# WM8904_mikroBUS_05.net
KiCad netlist of a schematic drawn in EasyEDA Pro
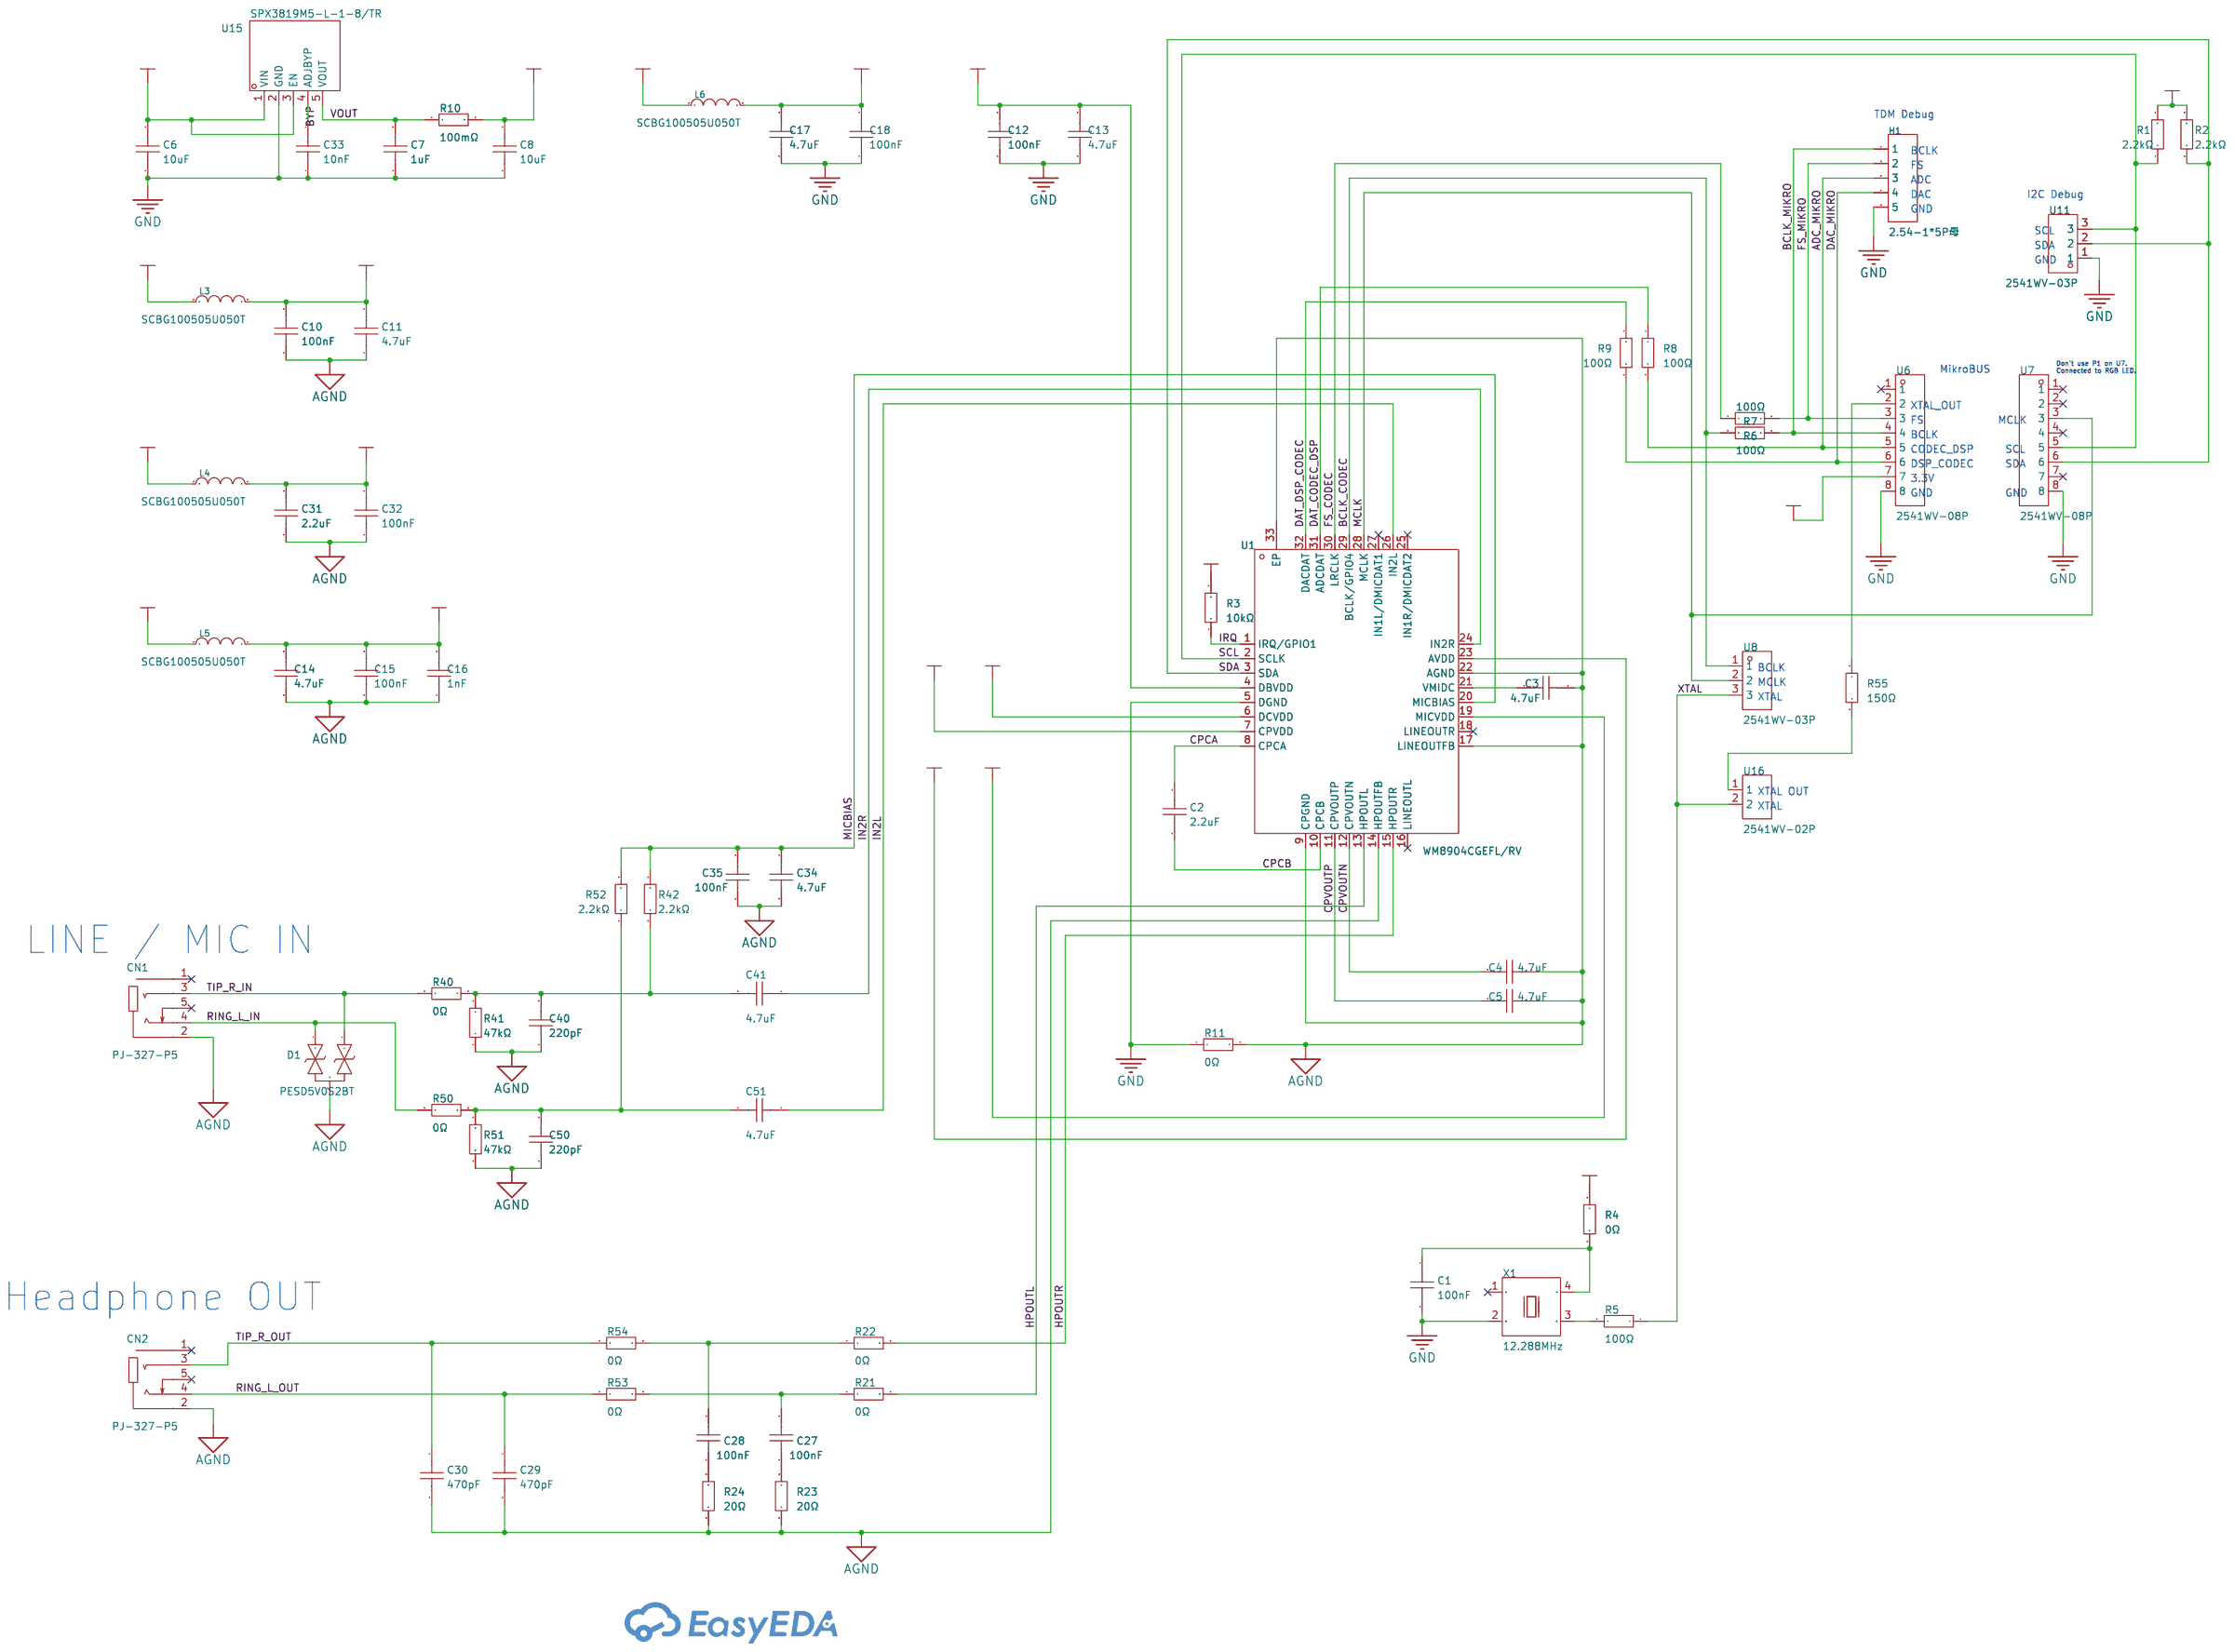
[diagram p0: schematic sheet]

(export (version "E")
  (design (tool "Eeschema 10.0.6"))
  (components
    (comp (ref "C1")
      (value "100nF")
      (footprint "easyedapro:C0603")
      (description "Capacitance:100nF Tolerance:±10% Tolerance:±10% Voltage Rating:50V Temperature Coefficient:X7R")
      (fields
        (field (name "Manufacturer Part") "CC0603KRX7R9BB104")
        (field (name "Manufacturer") "YAGEO(国巨)")
      )
      (libsource (lib "easyedapro") (part "CAP"))
    )
    (comp (ref "C2")
      (value "2.2uF")
      (footprint "easyedapro:C0603")
      (description "Capacitance:2.2uF Tolerance:±10% Tolerance:±10% Voltage Rating:16V Temperature Coefficient:X5R")
      (fields
        (field (name "Manufacturer Part") "CL10A225KO8NNNC")
        (field (name "Manufacturer") "SAMSUNG(三星)")
      )
      (libsource (lib "easyedapro") (part "CAP"))
    )
    (comp (ref "C3")
      (value "4.7uF")
      (footprint "easyedapro:C0603")
      (description "Capacitance:4.7uF Tolerance:±10% Tolerance:±10% Voltage Rating:16V Temperature Coefficient:X5R")
      (fields
        (field (name "Manufacturer Part") "CL10A475KO8NNNC")
        (field (name "Manufacturer") "SAMSUNG(三星)")
      )
      (libsource (lib "easyedapro") (part "CAP"))
    )
    (comp (ref "C4")
      (value "4.7uF")
      (footprint "easyedapro:C0603")
      (description "Capacitance:4.7uF Tolerance:±10% Tolerance:±10% Voltage Rating:16V Temperature Coefficient:X5R")
      (fields
        (field (name "Manufacturer Part") "CL10A475KO8NNNC")
        (field (name "Manufacturer") "SAMSUNG(三星)")
      )
      (libsource (lib "easyedapro") (part "CAP"))
    )
    (comp (ref "C5")
      (value "4.7uF")
      (footprint "easyedapro:C0603")
      (description "Capacitance:4.7uF Tolerance:±10% Tolerance:±10% Voltage Rating:16V Temperature Coefficient:X5R")
      (fields
        (field (name "Manufacturer Part") "CL10A475KO8NNNC")
        (field (name "Manufacturer") "SAMSUNG(三星)")
      )
      (libsource (lib "easyedapro") (part "CAP"))
    )
    (comp (ref "C6")
      (value "10uF")
      (footprint "easyedapro:C0603")
      (description "Capacitance:10uF Tolerance:±10% Tolerance:±10% Voltage Rating:10V Temperature Coefficient:X5R")
      (fields
        (field (name "Manufacturer Part") "CL10A106KP8NNNC")
        (field (name "Manufacturer") "SAMSUNG(三星)")
      )
      (libsource (lib "easyedapro") (part "CAP"))
    )
    (comp (ref "C7")
      (value "1uF")
      (footprint "easyedapro:C0603")
      (description "Capacitance:1uF Tolerance:±10% Tolerance:±10% Voltage Rating:50V Temperature Coefficient:X5R")
      (fields
        (field (name "Manufacturer Part") "CL10A105KB8NNNC")
        (field (name "Manufacturer") "SAMSUNG(三星)")
      )
      (libsource (lib "easyedapro") (part "CAP"))
    )
    (comp (ref "C8")
      (value "10uF")
      (footprint "easyedapro:C0603")
      (description "Capacitance:10uF Tolerance:±10% Tolerance:±10% Voltage Rating:10V Temperature Coefficient:X5R")
      (fields
        (field (name "Manufacturer Part") "CL10A106KP8NNNC")
        (field (name "Manufacturer") "SAMSUNG(三星)")
      )
      (libsource (lib "easyedapro") (part "CAP"))
    )
    (comp (ref "C10")
      (value "100nF")
      (footprint "easyedapro:C0603")
      (description "Capacitance:100nF Tolerance:±10% Tolerance:±10% Voltage Rating:50V Temperature Coefficient:X7R")
      (fields
        (field (name "Manufacturer Part") "CC0603KRX7R9BB104")
        (field (name "Manufacturer") "YAGEO(国巨)")
      )
      (libsource (lib "easyedapro") (part "CAP"))
    )
    (comp (ref "C11")
      (value "4.7uF")
      (footprint "easyedapro:C0603")
      (description "Capacitance:4.7uF Tolerance:±10% Tolerance:±10% Voltage Rating:16V Temperature Coefficient:X5R")
      (fields
        (field (name "Manufacturer Part") "CL10A475KO8NNNC")
        (field (name "Manufacturer") "SAMSUNG(三星)")
      )
      (libsource (lib "easyedapro") (part "CAP"))
    )
    (comp (ref "C12")
      (value "100nF")
      (footprint "easyedapro:C0603")
      (description "Capacitance:100nF Tolerance:±10% Tolerance:±10% Voltage Rating:50V Temperature Coefficient:X7R")
      (fields
        (field (name "Manufacturer Part") "CC0603KRX7R9BB104")
        (field (name "Manufacturer") "YAGEO(国巨)")
      )
      (libsource (lib "easyedapro") (part "CAP"))
    )
    (comp (ref "C13")
      (value "4.7uF")
      (footprint "easyedapro:C0603")
      (description "Capacitance:4.7uF Tolerance:±10% Tolerance:±10% Voltage Rating:16V Temperature Coefficient:X5R")
      (fields
        (field (name "Manufacturer Part") "CL10A475KO8NNNC")
        (field (name "Manufacturer") "SAMSUNG(三星)")
      )
      (libsource (lib "easyedapro") (part "CAP"))
    )
    (comp (ref "C14")
      (value "4.7uF")
      (footprint "easyedapro:C0603")
      (description "Capacitance:4.7uF Tolerance:±10% Tolerance:±10% Voltage Rating:16V Temperature Coefficient:X5R")
      (fields
        (field (name "Manufacturer Part") "CL10A475KO8NNNC")
        (field (name "Manufacturer") "SAMSUNG(三星)")
      )
      (libsource (lib "easyedapro") (part "CAP"))
    )
    (comp (ref "C15")
      (value "100nF")
      (footprint "easyedapro:C0603")
      (description "Capacitance:100nF Tolerance:±10% Tolerance:±10% Voltage Rating:50V Temperature Coefficient:X7R")
      (fields
        (field (name "Manufacturer Part") "CC0603KRX7R9BB104")
        (field (name "Manufacturer") "YAGEO(国巨)")
      )
      (libsource (lib "easyedapro") (part "CAP"))
    )
    (comp (ref "C16")
      (value "1nF")
      (footprint "easyedapro:C0603")
      (description "Capacitance:1nF Tolerance:±10% Tolerance:±10% Voltage Rating:50V Temperature Coefficient:X7R")
      (fields
        (field (name "Manufacturer Part") "CL10B102KB8NNNC")
        (field (name "Manufacturer") "SAMSUNG(三星)")
      )
      (libsource (lib "easyedapro") (part "CAP"))
    )
    (comp (ref "C17")
      (value "4.7uF")
      (footprint "easyedapro:C0603")
      (description "Capacitance:4.7uF Tolerance:±10% Tolerance:±10% Voltage Rating:16V Temperature Coefficient:X5R")
      (fields
        (field (name "Manufacturer Part") "CL10A475KO8NNNC")
        (field (name "Manufacturer") "SAMSUNG(三星)")
      )
      (libsource (lib "easyedapro") (part "CAP"))
    )
    (comp (ref "C18")
      (value "100nF")
      (footprint "easyedapro:C0603")
      (description "Capacitance:100nF Tolerance:±10% Tolerance:±10% Voltage Rating:50V Temperature Coefficient:X7R")
      (fields
        (field (name "Manufacturer Part") "CC0603KRX7R9BB104")
        (field (name "Manufacturer") "YAGEO(国巨)")
      )
      (libsource (lib "easyedapro") (part "CAP"))
    )
    (comp (ref "C27")
      (value "100nF")
      (footprint "easyedapro:C0603")
      (description "Capacitance:100nF Tolerance:±10% Tolerance:±10% Voltage Rating:50V Temperature Coefficient:X7R")
      (fields
        (field (name "Manufacturer Part") "CC0603KRX7R9BB104")
        (field (name "Manufacturer") "YAGEO(国巨)")
      )
      (libsource (lib "easyedapro") (part "CAP"))
    )
    (comp (ref "C28")
      (value "100nF")
      (footprint "easyedapro:C0603")
      (description "Capacitance:100nF Tolerance:±10% Tolerance:±10% Voltage Rating:50V Temperature Coefficient:X7R")
      (fields
        (field (name "Manufacturer Part") "CC0603KRX7R9BB104")
        (field (name "Manufacturer") "YAGEO(国巨)")
      )
      (libsource (lib "easyedapro") (part "CAP"))
    )
    (comp (ref "C29")
      (value "470pF")
      (footprint "easyedapro:C0603")
      (description "Capacitance:470pF Tolerance:±10% Tolerance:±10% Voltage Rating:50V Temperature Coefficient:X7R")
      (fields (field (name "Manufacturer Part") "0603B471K500NT") (field (name "Manufacturer") "FH(风华)"))
      (libsource (lib "easyedapro") (part "CAP"))
    )
    (comp (ref "C30")
      (value "470pF")
      (footprint "easyedapro:C0603")
      (description "Capacitance:470pF Tolerance:±10% Tolerance:±10% Voltage Rating:50V Temperature Coefficient:X7R")
      (fields (field (name "Manufacturer Part") "0603B471K500NT") (field (name "Manufacturer") "FH(风华)"))
      (libsource (lib "easyedapro") (part "CAP"))
    )
    (comp (ref "C31")
      (value "2.2uF")
      (footprint "easyedapro:C0603")
      (description "Capacitance:2.2uF Tolerance:±10% Tolerance:±10% Voltage Rating:16V Temperature Coefficient:X5R")
      (fields
        (field (name "Manufacturer Part") "CL10A225KO8NNNC")
        (field (name "Manufacturer") "SAMSUNG(三星)")
      )
      (libsource (lib "easyedapro") (part "CAP"))
    )
    (comp (ref "C32")
      (value "100nF")
      (footprint "easyedapro:C0603")
      (description "Capacitance:100nF Tolerance:±10% Tolerance:±10% Voltage Rating:50V Temperature Coefficient:X7R")
      (fields
        (field (name "Manufacturer Part") "CC0603KRX7R9BB104")
        (field (name "Manufacturer") "YAGEO(国巨)")
      )
      (libsource (lib "easyedapro") (part "CAP"))
    )
    (comp (ref "C33")
      (value "10nF")
      (footprint "easyedapro:C0603")
      (description "Capacitance:10nF Tolerance:±10% Tolerance:±10% Voltage Rating:50V Temperature Coefficient:X7R")
      (fields (field (name "Manufacturer Part") "0603B103K500NT") (field (name "Manufacturer") "FH(风华)"))
      (libsource (lib "easyedapro") (part "CAP"))
    )
    (comp (ref "C34")
      (value "4.7uF")
      (footprint "easyedapro:C0603")
      (description "Capacitance:4.7uF Tolerance:±10% Tolerance:±10% Voltage Rating:16V Temperature Coefficient:X5R")
      (fields
        (field (name "Manufacturer Part") "CL10A475KO8NNNC")
        (field (name "Manufacturer") "SAMSUNG(三星)")
      )
      (libsource (lib "easyedapro") (part "CAP"))
    )
    (comp (ref "C35")
      (value "100nF")
      (footprint "easyedapro:C0603")
      (description "Capacitance:100nF Tolerance:±10% Tolerance:±10% Voltage Rating:50V Temperature Coefficient:X7R")
      (fields
        (field (name "Manufacturer Part") "CC0603KRX7R9BB104")
        (field (name "Manufacturer") "YAGEO(国巨)")
      )
      (libsource (lib "easyedapro") (part "CAP"))
    )
    (comp (ref "C40")
      (value "220pF")
      (footprint "easyedapro:C0603")
      (description "Capacitance:220pF Tolerance:±10% Tolerance:±10% Voltage Rating:50V Temperature Coefficient:X7R")
      (fields
        (field (name "Manufacturer Part") "CL10B221KB8NNNC")
        (field (name "Manufacturer") "SAMSUNG(三星)")
      )
      (libsource (lib "easyedapro") (part "CAP"))
    )
    (comp (ref "C41")
      (value "4.7uF")
      (footprint "easyedapro:C0603")
      (description "Capacitance:4.7uF Tolerance:±10% Tolerance:±10% Voltage Rating:16V Temperature Coefficient:X5R")
      (fields
        (field (name "Manufacturer Part") "CL10A475KO8NNNC")
        (field (name "Manufacturer") "SAMSUNG(三星)")
      )
      (libsource (lib "easyedapro") (part "CAP"))
    )
    (comp (ref "C50")
      (value "220pF")
      (footprint "easyedapro:C0603")
      (description "Capacitance:220pF Tolerance:±10% Tolerance:±10% Voltage Rating:50V Temperature Coefficient:X7R")
      (fields
        (field (name "Manufacturer Part") "CL10B221KB8NNNC")
        (field (name "Manufacturer") "SAMSUNG(三星)")
      )
      (libsource (lib "easyedapro") (part "CAP"))
    )
    (comp (ref "C51")
      (value "4.7uF")
      (footprint "easyedapro:C0603")
      (description "Capacitance:4.7uF Tolerance:±10% Tolerance:±10% Voltage Rating:16V Temperature Coefficient:X5R")
      (fields
        (field (name "Manufacturer Part") "CL10A475KO8NNNC")
        (field (name "Manufacturer") "SAMSUNG(三星)")
      )
      (libsource (lib "easyedapro") (part "CAP"))
    )
    (comp (ref "CN1")
      (value "PJ-327-P5")
      (footprint "easyedapro:AUDIO-TH_PJ-327-P5")
      (fields (field (name "Manufacturer") "SOFNG(硕方)"))
      (libsource (lib "easyedapro") (part "PJ-327-P5"))
    )
    (comp (ref "CN2")
      (value "PJ-327-P5")
      (footprint "easyedapro:AUDIO-TH_PJ-327-P5")
      (fields (field (name "Manufacturer") "SOFNG(硕方)"))
      (libsource (lib "easyedapro") (part "PJ-327-P5"))
    )
    (comp (ref "D1")
      (value "PESD5V0S2BT")
      (footprint "easyedapro:SOT-23-3_L2.9-W1.3-P1.90-LS2.4-BR")
      (fields (field (name "Manufacturer") "GOODWORK(固得沃克)"))
      (libsource (lib "easyedapro") (part "PESD5V0S2BT_C28310457"))
    )
    (comp (ref "H1")
      (value "2.54-1*5P母")
      (footprint "easyedapro:HDR-TH_5P-P2.54-V-F")
      (fields (field (name "Manufacturer") "BOOMELE(博穆精密)"))
      (libsource (lib "easyedapro") (part "Header-Female-2.54_1x5"))
    )
    (comp (ref "L3")
      (value "SCBG100505U050T")
      (footprint "easyedapro:L0402")
      (fields (field (name "Manufacturer") "Yanchuang(研创)"))
      (libsource (lib "easyedapro") (part "SCBG100505U050T"))
    )
    (comp (ref "L4")
      (value "SCBG100505U050T")
      (footprint "easyedapro:L0402")
      (fields (field (name "Manufacturer") "Yanchuang(研创)"))
      (libsource (lib "easyedapro") (part "SCBG100505U050T"))
    )
    (comp (ref "L5")
      (value "SCBG100505U050T")
      (footprint "easyedapro:L0402")
      (fields (field (name "Manufacturer") "Yanchuang(研创)"))
      (libsource (lib "easyedapro") (part "SCBG100505U050T"))
    )
    (comp (ref "L6")
      (value "SCBG100505U050T")
      (footprint "easyedapro:L0402")
      (fields (field (name "Manufacturer") "Yanchuang(研创)"))
      (libsource (lib "easyedapro") (part "SCBG100505U050T"))
    )
    (comp (ref "R1")
      (value "2.2kΩ")
      (footprint "easyedapro:R0603")
      (fields
        (field (name "Manufacturer Part") "0603WAF2201T5E")
        (field (name "Manufacturer") "UNI-ROYAL(厚声)")
      )
      (libsource (lib "easyedapro") (part "Res"))
    )
    (comp (ref "R2")
      (value "2.2kΩ")
      (footprint "easyedapro:R0603")
      (fields
        (field (name "Manufacturer Part") "0603WAF2201T5E")
        (field (name "Manufacturer") "UNI-ROYAL(厚声)")
      )
      (libsource (lib "easyedapro") (part "Res"))
    )
    (comp (ref "R3")
      (value "10kΩ")
      (footprint "easyedapro:R0603")
      (fields
        (field (name "Manufacturer Part") "0603WAF1002T5E")
        (field (name "Manufacturer") "UNI-ROYAL(厚声)")
      )
      (libsource (lib "easyedapro") (part "Res"))
    )
    (comp (ref "R4")
      (value "0Ω")
      (footprint "easyedapro:R0603")
      (fields
        (field (name "Manufacturer Part") "0603WAF0000T5E")
        (field (name "Manufacturer") "UNI-ROYAL(厚声)")
      )
      (libsource (lib "easyedapro") (part "Res"))
    )
    (comp (ref "R5")
      (value "100Ω")
      (footprint "easyedapro:R0603")
      (fields
        (field (name "Manufacturer Part") "0603WAF1000T5E")
        (field (name "Manufacturer") "UNI-ROYAL(厚声)")
      )
      (libsource (lib "easyedapro") (part "Res"))
    )
    (comp (ref "R6")
      (value "100Ω")
      (footprint "easyedapro:R0603")
      (fields
        (field (name "Manufacturer Part") "0603WAF1000T5E")
        (field (name "Manufacturer") "UNI-ROYAL(厚声)")
      )
      (libsource (lib "easyedapro") (part "Res"))
    )
    (comp (ref "R7")
      (value "100Ω")
      (footprint "easyedapro:R0603")
      (fields
        (field (name "Manufacturer Part") "0603WAF1000T5E")
        (field (name "Manufacturer") "UNI-ROYAL(厚声)")
      )
      (libsource (lib "easyedapro") (part "Res"))
    )
    (comp (ref "R8")
      (value "100Ω")
      (footprint "easyedapro:R0603")
      (fields
        (field (name "Manufacturer Part") "0603WAF1000T5E")
        (field (name "Manufacturer") "UNI-ROYAL(厚声)")
      )
      (libsource (lib "easyedapro") (part "Res"))
    )
    (comp (ref "R9")
      (value "100Ω")
      (footprint "easyedapro:R0603")
      (fields
        (field (name "Manufacturer Part") "0603WAF1000T5E")
        (field (name "Manufacturer") "UNI-ROYAL(厚声)")
      )
      (libsource (lib "easyedapro") (part "Res"))
    )
    (comp (ref "R10")
      (value "100mΩ")
      (footprint "easyedapro:R0603")
      (fields
        (field (name "Manufacturer Part") "0603WAJ010KT5E")
        (field (name "Manufacturer") "UNI-ROYAL(厚声)")
      )
      (libsource (lib "easyedapro") (part "Res"))
    )
    (comp (ref "R11")
      (value "0Ω")
      (footprint "easyedapro:R0603")
      (fields
        (field (name "Manufacturer Part") "0603WAF0000T5E")
        (field (name "Manufacturer") "UNI-ROYAL(厚声)")
      )
      (libsource (lib "easyedapro") (part "Res"))
    )
    (comp (ref "R21")
      (value "0Ω")
      (footprint "easyedapro:R0603")
      (fields
        (field (name "Manufacturer Part") "0603WAF0000T5E")
        (field (name "Manufacturer") "UNI-ROYAL(厚声)")
      )
      (libsource (lib "easyedapro") (part "Res"))
    )
    (comp (ref "R22")
      (value "0Ω")
      (footprint "easyedapro:R0603")
      (fields
        (field (name "Manufacturer Part") "0603WAF0000T5E")
        (field (name "Manufacturer") "UNI-ROYAL(厚声)")
      )
      (libsource (lib "easyedapro") (part "Res"))
    )
    (comp (ref "R23")
      (value "20Ω")
      (footprint "easyedapro:R0603")
      (fields
        (field (name "Manufacturer Part") "0603WAF200JT5E")
        (field (name "Manufacturer") "UNI-ROYAL(厚声)")
      )
      (libsource (lib "easyedapro") (part "Res"))
    )
    (comp (ref "R24")
      (value "20Ω")
      (footprint "easyedapro:R0603")
      (fields
        (field (name "Manufacturer Part") "0603WAF200JT5E")
        (field (name "Manufacturer") "UNI-ROYAL(厚声)")
      )
      (libsource (lib "easyedapro") (part "Res"))
    )
    (comp (ref "R40")
      (value "0Ω")
      (footprint "easyedapro:R0603")
      (fields
        (field (name "Manufacturer Part") "0603WAF0000T5E")
        (field (name "Manufacturer") "UNI-ROYAL(厚声)")
      )
      (libsource (lib "easyedapro") (part "Res"))
    )
    (comp (ref "R41")
      (value "47kΩ")
      (footprint "easyedapro:R0603")
      (fields
        (field (name "Manufacturer Part") "0603WAF4702T5E")
        (field (name "Manufacturer") "UNI-ROYAL(厚声)")
      )
      (libsource (lib "easyedapro") (part "Res"))
    )
    (comp (ref "R42")
      (value "2.2kΩ")
      (footprint "easyedapro:R0603")
      (fields
        (field (name "Manufacturer Part") "0603WAF2201T5E")
        (field (name "Manufacturer") "UNI-ROYAL(厚声)")
      )
      (libsource (lib "easyedapro") (part "Res"))
    )
    (comp (ref "R50")
      (value "0Ω")
      (footprint "easyedapro:R0603")
      (fields
        (field (name "Manufacturer Part") "0603WAF0000T5E")
        (field (name "Manufacturer") "UNI-ROYAL(厚声)")
      )
      (libsource (lib "easyedapro") (part "Res"))
    )
    (comp (ref "R51")
      (value "47kΩ")
      (footprint "easyedapro:R0603")
      (fields
        (field (name "Manufacturer Part") "0603WAF4702T5E")
        (field (name "Manufacturer") "UNI-ROYAL(厚声)")
      )
      (libsource (lib "easyedapro") (part "Res"))
    )
    (comp (ref "R52")
      (value "2.2kΩ")
      (footprint "easyedapro:R0603")
      (fields
        (field (name "Manufacturer Part") "0603WAF2201T5E")
        (field (name "Manufacturer") "UNI-ROYAL(厚声)")
      )
      (libsource (lib "easyedapro") (part "Res"))
    )
    (comp (ref "R53")
      (value "0Ω")
      (footprint "easyedapro:R0603")
      (fields
        (field (name "Manufacturer Part") "0603WAF0000T5E")
        (field (name "Manufacturer") "UNI-ROYAL(厚声)")
      )
      (libsource (lib "easyedapro") (part "Res"))
    )
    (comp (ref "R54")
      (value "0Ω")
      (footprint "easyedapro:R0603")
      (fields
        (field (name "Manufacturer Part") "0603WAF0000T5E")
        (field (name "Manufacturer") "UNI-ROYAL(厚声)")
      )
      (libsource (lib "easyedapro") (part "Res"))
    )
    (comp (ref "R55")
      (value "150Ω")
      (footprint "easyedapro:R0603")
      (fields
        (field (name "Manufacturer Part") "0603WAF1500T5E")
        (field (name "Manufacturer") "UNI-ROYAL(厚声)")
      )
      (libsource (lib "easyedapro") (part "Res"))
    )
    (comp (ref "U1")
      (value "WM8904CGEFL/RV")
      (footprint "easyedapro:QFN-32_L4.0-W4.0-P0.40-BL-EP2.7")
      (fields (field (name "Manufacturer") "Cirrus Logic(凌云)"))
      (libsource (lib "easyedapro") (part "WM8904CGEFL/RV"))
    )
    (comp (ref "U6")
      (value "2541WV-08P")
      (footprint "easyedapro:HDR-TH_8P-P2.54-V-M-4")
      (fields (field (name "Manufacturer") "HanElectricity(瀚源)"))
      (libsource (lib "easyedapro") (part "2541WV-08P"))
    )
    (comp (ref "U7")
      (value "2541WV-08P")
      (footprint "easyedapro:HDR-TH_8P-P2.54-V-M-4")
      (fields (field (name "Manufacturer") "HanElectricity(瀚源)"))
      (libsource (lib "easyedapro") (part "2541WV-08P"))
    )
    (comp (ref "U8")
      (value "2541WV-03P")
      (footprint "easyedapro:HDR-TH_3P-P2.54-V-M-2")
      (fields (field (name "Manufacturer") "HanElectricity(瀚源)"))
      (libsource (lib "easyedapro") (part "2541WV-03P"))
    )
    (comp (ref "U11")
      (value "2541WV-03P")
      (footprint "easyedapro:HDR-TH_3P-P2.54-V-M-2")
      (fields (field (name "Manufacturer") "HanElectricity(瀚源)"))
      (libsource (lib "easyedapro") (part "2541WV-03P"))
    )
    (comp (ref "U15")
      (value "SPX3819M5-L-1-8/TR")
      (footprint "easyedapro:SOT-23-5_L3.0-W1.7-P0.95-LS2.8-TL")
      (fields (field (name "Manufacturer") "MaxLinear(迈凌)"))
      (libsource (lib "easyedapro") (part "SPX3819M5-L-1-8"))
    )
    (comp (ref "U16")
      (value "2541WV-02P")
      (footprint "easyedapro:HDR-TH_2P-P2.54-V-M-1")
      (fields (field (name "Manufacturer") "HanElectricity(瀚源)"))
      (libsource (lib "easyedapro") (part "2541WV-02P"))
    )
    (comp (ref "X1")
      (value "12.288MHz")
      (footprint "easyedapro:OSC-SMD_4P-L2.5-W2.0-BL")
      (fields (field (name "Manufacturer Part") "X1G0041710019") (field (name "Manufacturer") "EPSON(爱普生)"))
      (libsource (lib "easyedapro") (part "X1G004171001900"))
    )
  )
  (nets
    (net (code "1") (name "+3.3V") (class "Default")
      (node (ref "C12") (pin "2") (pinfunction "2_2") (pintype "input"))
      (node (ref "C13") (pin "2") (pinfunction "2_2") (pintype "input"))
      (node (ref "C6") (pin "2") (pinfunction "2_2") (pintype "input"))
      (node (ref "L3") (pin "1") (pinfunction "1_1") (pintype "input"))
      (node (ref "R1") (pin "2") (pinfunction "2_2") (pintype "input"))
      (node (ref "R2") (pin "2") (pinfunction "2_2") (pintype "input"))
      (node (ref "R3") (pin "2") (pinfunction "2_2") (pintype "input"))
      (node (ref "R4") (pin "2") (pinfunction "2_2") (pintype "input"))
      (node (ref "U1") (pin "4") (pinfunction "DBVDD_4") (pintype "unspecified"))
      (node (ref "U15") (pin "1") (pinfunction "VIN_1") (pintype "unspecified"))
      (node (ref "U15") (pin "3") (pinfunction "EN_3") (pintype "unspecified"))
      (node (ref "U6") (pin "7") (pinfunction "7_7") (pintype "unspecified"))
    )
    (net (code "2") (name "/ADC_MIKRO") (class "Default")
      (node (ref "H1") (pin "3") (pinfunction "3_3") (pintype "input"))
      (node (ref "R8") (pin "2") (pinfunction "2_2") (pintype "input"))
      (node (ref "U6") (pin "5") (pinfunction "5_5") (pintype "unspecified"))
    )
    (net (code "3") (name "/BCLK_CODEC") (class "Default")
      (node (ref "R6") (pin "2") (pinfunction "2_2") (pintype "input"))
      (node (ref "U1") (pin "29") (pinfunction "BCLK/GPIO4_29") (pintype "unspecified"))
      (node (ref "U8") (pin "1") (pinfunction "1_1") (pintype "unspecified"))
    )
    (net (code "4") (name "/BCLK_MIKRO") (class "Default")
      (node (ref "H1") (pin "1") (pinfunction "1_1") (pintype "input"))
      (node (ref "R6") (pin "1") (pinfunction "1_1") (pintype "input"))
      (node (ref "U6") (pin "4") (pinfunction "4_4") (pintype "unspecified"))
    )
    (net (code "5") (name "/BYP") (class "Default")
      (node (ref "C33") (pin "2") (pinfunction "2_2") (pintype "input"))
      (node (ref "U15") (pin "4") (pinfunction "ADJBYP_4") (pintype "unspecified"))
    )
    (net (code "6") (name "/CPCA") (class "Default")
      (node (ref "C2") (pin "1") (pinfunction "1_1") (pintype "input"))
      (node (ref "U1") (pin "8") (pinfunction "CPCA_8") (pintype "unspecified"))
    )
    (net (code "7") (name "/CPCB") (class "Default")
      (node (ref "C2") (pin "2") (pinfunction "2_2") (pintype "input"))
      (node (ref "U1") (pin "10") (pinfunction "CPCB_10") (pintype "unspecified"))
    )
    (net (code "8") (name "/CPVOUTN") (class "Default")
      (node (ref "C4") (pin "2") (pinfunction "2_2") (pintype "input"))
      (node (ref "U1") (pin "12") (pinfunction "CPVOUTN_12") (pintype "unspecified"))
    )
    (net (code "9") (name "/CPVOUTP") (class "Default")
      (node (ref "C5") (pin "2") (pinfunction "2_2") (pintype "input"))
      (node (ref "U1") (pin "11") (pinfunction "CPVOUTP_11") (pintype "unspecified"))
    )
    (net (code "10") (name "/DAC_MIKRO") (class "Default")
      (node (ref "H1") (pin "4") (pinfunction "4_4") (pintype "input"))
      (node (ref "R9") (pin "2") (pinfunction "2_2") (pintype "input"))
      (node (ref "U6") (pin "6") (pinfunction "6_6") (pintype "unspecified"))
    )
    (net (code "11") (name "/DAT_CODEC_DSP") (class "Default")
      (node (ref "R8") (pin "1") (pinfunction "1_1") (pintype "input"))
      (node (ref "U1") (pin "31") (pinfunction "ADCDAT_31") (pintype "unspecified"))
    )
    (net (code "12") (name "/DAT_DSP_CODEC") (class "Default")
      (node (ref "R9") (pin "1") (pinfunction "1_1") (pintype "input"))
      (node (ref "U1") (pin "32") (pinfunction "DACDAT_32") (pintype "unspecified"))
    )
    (net (code "13") (name "/FS_CODEC") (class "Default")
      (node (ref "R7") (pin "1") (pinfunction "1_1") (pintype "input"))
      (node (ref "U1") (pin "30") (pinfunction "LRCLK_30") (pintype "unspecified"))
    )
    (net (code "14") (name "/FS_MIKRO") (class "Default")
      (node (ref "H1") (pin "2") (pinfunction "2_2") (pintype "input"))
      (node (ref "R7") (pin "2") (pinfunction "2_2") (pintype "input"))
      (node (ref "U6") (pin "3") (pinfunction "3_3") (pintype "unspecified"))
    )
    (net (code "15") (name "/HPOUTL") (class "Default")
      (node (ref "R21") (pin "2") (pinfunction "2_2") (pintype "input"))
      (node (ref "U1") (pin "13") (pinfunction "HPOUTL_13") (pintype "unspecified"))
    )
    (net (code "16") (name "/HPOUTR") (class "Default")
      (node (ref "R22") (pin "2") (pinfunction "2_2") (pintype "input"))
      (node (ref "U1") (pin "15") (pinfunction "HPOUTR_15") (pintype "unspecified"))
    )
    (net (code "17") (name "/IN2L") (class "Default")
      (node (ref "C51") (pin "1") (pinfunction "1_1") (pintype "input"))
      (node (ref "U1") (pin "26") (pinfunction "IN2L_26") (pintype "unspecified"))
    )
    (net (code "18") (name "/IN2R") (class "Default")
      (node (ref "C41") (pin "1") (pinfunction "1_1") (pintype "input"))
      (node (ref "U1") (pin "24") (pinfunction "IN2R_24") (pintype "unspecified"))
    )
    (net (code "19") (name "/IRQ") (class "Default")
      (node (ref "R3") (pin "1") (pinfunction "1_1") (pintype "input"))
      (node (ref "U1") (pin "1") (pinfunction "IRQ/GPIO1_1") (pintype "unspecified"))
    )
    (net (code "20") (name "/MCLK") (class "Default")
      (node (ref "U1") (pin "28") (pinfunction "MCLK_28") (pintype "unspecified"))
      (node (ref "U7") (pin "3") (pinfunction "3_3") (pintype "unspecified"))
      (node (ref "U8") (pin "2") (pinfunction "2_2") (pintype "unspecified"))
    )
    (net (code "21") (name "/MICBIAS") (class "Default")
      (node (ref "C34") (pin "1") (pinfunction "1_1") (pintype "input"))
      (node (ref "C35") (pin "1") (pinfunction "1_1") (pintype "input"))
      (node (ref "R42") (pin "2") (pinfunction "2_2") (pintype "input"))
      (node (ref "R52") (pin "2") (pinfunction "2_2") (pintype "input"))
      (node (ref "U1") (pin "20") (pinfunction "MICBIAS_20") (pintype "unspecified"))
    )
    (net (code "22") (name "/RING_L_IN") (class "Default")
      (node (ref "CN1") (pin "4") (pinfunction "4_4") (pintype "unspecified"))
      (node (ref "D1") (pin "2") (pinfunction "2_2") (pintype "unspecified"))
      (node (ref "R50") (pin "1") (pinfunction "1_1") (pintype "input"))
    )
    (net (code "23") (name "/RING_L_OUT") (class "Default")
      (node (ref "C29") (pin "1") (pinfunction "1_1") (pintype "input"))
      (node (ref "CN2") (pin "4") (pinfunction "4_4") (pintype "unspecified"))
      (node (ref "R53") (pin "1") (pinfunction "1_1") (pintype "input"))
    )
    (net (code "24") (name "/SCL") (class "Default")
      (node (ref "R1") (pin "1") (pinfunction "1_1") (pintype "input"))
      (node (ref "U1") (pin "2") (pinfunction "SCLK_2") (pintype "unspecified"))
      (node (ref "U11") (pin "3") (pinfunction "3_3") (pintype "unspecified"))
      (node (ref "U7") (pin "5") (pinfunction "5_5") (pintype "unspecified"))
    )
    (net (code "25") (name "/SDA") (class "Default")
      (node (ref "R2") (pin "1") (pinfunction "1_1") (pintype "input"))
      (node (ref "U1") (pin "3") (pinfunction "SDA_3") (pintype "unspecified"))
      (node (ref "U11") (pin "2") (pinfunction "2_2") (pintype "unspecified"))
      (node (ref "U7") (pin "6") (pinfunction "6_6") (pintype "unspecified"))
    )
    (net (code "26") (name "/TIP_R_IN") (class "Default")
      (node (ref "CN1") (pin "3") (pinfunction "3_3") (pintype "unspecified"))
      (node (ref "D1") (pin "1") (pinfunction "1_1") (pintype "unspecified"))
      (node (ref "R40") (pin "1") (pinfunction "1_1") (pintype "input"))
    )
    (net (code "27") (name "/TIP_R_OUT") (class "Default")
      (node (ref "C30") (pin "1") (pinfunction "1_1") (pintype "input"))
      (node (ref "CN2") (pin "3") (pinfunction "3_3") (pintype "unspecified"))
      (node (ref "R54") (pin "1") (pinfunction "1_1") (pintype "input"))
    )
    (net (code "28") (name "/VOUT") (class "Default")
      (node (ref "C7") (pin "2") (pinfunction "2_2") (pintype "input"))
      (node (ref "R10") (pin "1") (pinfunction "1_1") (pintype "input"))
      (node (ref "U15") (pin "5") (pinfunction "VOUT_5") (pintype "unspecified"))
    )
    (net (code "29") (name "/XTAL") (class "Default")
      (node (ref "R5") (pin "1") (pinfunction "1_1") (pintype "input"))
      (node (ref "U16") (pin "2") (pinfunction "2_2") (pintype "unspecified"))
      (node (ref "U8") (pin "3") (pinfunction "3_3") (pintype "unspecified"))
    )
    (net (code "30") (name "AGND") (class "Default")
      (node (ref "C10") (pin "1") (pinfunction "1_1") (pintype "input"))
      (node (ref "C11") (pin "1") (pinfunction "1_1") (pintype "input"))
      (node (ref "C14") (pin "1") (pinfunction "1_1") (pintype "input"))
      (node (ref "C15") (pin "1") (pinfunction "1_1") (pintype "input"))
      (node (ref "C16") (pin "1") (pinfunction "1_1") (pintype "input"))
      (node (ref "C29") (pin "2") (pinfunction "2_2") (pintype "input"))
      (node (ref "C3") (pin "2") (pinfunction "2_2") (pintype "input"))
      (node (ref "C30") (pin "2") (pinfunction "2_2") (pintype "input"))
      (node (ref "C31") (pin "1") (pinfunction "1_1") (pintype "input"))
      (node (ref "C32") (pin "1") (pinfunction "1_1") (pintype "input"))
      (node (ref "C34") (pin "2") (pinfunction "2_2") (pintype "input"))
      (node (ref "C35") (pin "2") (pinfunction "2_2") (pintype "input"))
      (node (ref "C4") (pin "1") (pinfunction "1_1") (pintype "input"))
      (node (ref "C40") (pin "1") (pinfunction "1_1") (pintype "input"))
      (node (ref "C5") (pin "1") (pinfunction "1_1") (pintype "input"))
      (node (ref "C50") (pin "1") (pinfunction "1_1") (pintype "input"))
      (node (ref "CN1") (pin "2") (pinfunction "2_2") (pintype "unspecified"))
      (node (ref "CN2") (pin "2") (pinfunction "2_2") (pintype "unspecified"))
      (node (ref "D1") (pin "3") (pinfunction "3_3") (pintype "unspecified"))
      (node (ref "R11") (pin "2") (pinfunction "2_2") (pintype "input"))
      (node (ref "R23") (pin "1") (pinfunction "1_1") (pintype "input"))
      (node (ref "R24") (pin "1") (pinfunction "1_1") (pintype "input"))
      (node (ref "R41") (pin "1") (pinfunction "1_1") (pintype "input"))
      (node (ref "R51") (pin "1") (pinfunction "1_1") (pintype "input"))
      (node (ref "U1") (pin "14") (pinfunction "HPOUTFB_14") (pintype "unspecified"))
      (node (ref "U1") (pin "17") (pinfunction "LINEOUTFB_17") (pintype "unspecified"))
      (node (ref "U1") (pin "22") (pinfunction "AGND_22") (pintype "unspecified"))
      (node (ref "U1") (pin "33") (pinfunction "EP_33") (pintype "unspecified"))
      (node (ref "U1") (pin "9") (pinfunction "CPGND_9") (pintype "unspecified"))
    )
    (net (code "31") (name "AVDD") (class "Default")
      (node (ref "C31") (pin "2") (pinfunction "2_2") (pintype "input"))
      (node (ref "C32") (pin "2") (pinfunction "2_2") (pintype "input"))
      (node (ref "L4") (pin "2") (pinfunction "2_2") (pintype "input"))
      (node (ref "U1") (pin "23") (pinfunction "AVDD_23") (pintype "unspecified"))
    )
    (net (code "32") (name "CPVDD") (class "Default")
      (node (ref "C14") (pin "2") (pinfunction "2_2") (pintype "input"))
      (node (ref "C15") (pin "2") (pinfunction "2_2") (pintype "input"))
      (node (ref "C16") (pin "2") (pinfunction "2_2") (pintype "input"))
      (node (ref "L5") (pin "2") (pinfunction "2_2") (pintype "input"))
      (node (ref "U1") (pin "7") (pinfunction "CPVDD_7") (pintype "unspecified"))
    )
    (net (code "33") (name "DCVDD") (class "Default")
      (node (ref "C17") (pin "2") (pinfunction "2_2") (pintype "input"))
      (node (ref "C18") (pin "2") (pinfunction "2_2") (pintype "input"))
      (node (ref "L6") (pin "2") (pinfunction "2_2") (pintype "input"))
      (node (ref "U1") (pin "6") (pinfunction "DCVDD_6") (pintype "unspecified"))
    )
    (net (code "34") (name "GND") (class "Default")
      (node (ref "C1") (pin "2") (pinfunction "2_2") (pintype "input"))
      (node (ref "C12") (pin "1") (pinfunction "1_1") (pintype "input"))
      (node (ref "C13") (pin "1") (pinfunction "1_1") (pintype "input"))
      (node (ref "C17") (pin "1") (pinfunction "1_1") (pintype "input"))
      (node (ref "C18") (pin "1") (pinfunction "1_1") (pintype "input"))
      (node (ref "C33") (pin "1") (pinfunction "1_1") (pintype "input"))
      (node (ref "C6") (pin "1") (pinfunction "1_1") (pintype "input"))
      (node (ref "C7") (pin "1") (pinfunction "1_1") (pintype "input"))
      (node (ref "C8") (pin "1") (pinfunction "1_1") (pintype "input"))
      (node (ref "H1") (pin "5") (pinfunction "5_5") (pintype "input"))
      (node (ref "R11") (pin "1") (pinfunction "1_1") (pintype "input"))
      (node (ref "U1") (pin "5") (pinfunction "DGND_5") (pintype "unspecified"))
      (node (ref "U11") (pin "1") (pinfunction "1_1") (pintype "unspecified"))
      (node (ref "U15") (pin "2") (pinfunction "GND_2") (pintype "unspecified"))
      (node (ref "U6") (pin "8") (pinfunction "8_8") (pintype "unspecified"))
      (node (ref "U7") (pin "8") (pinfunction "8_8") (pintype "unspecified"))
      (node (ref "X1") (pin "2") (pinfunction "GND_2") (pintype "unspecified"))
    )
    (net (code "35") (name "MICVDD") (class "Default")
      (node (ref "C10") (pin "2") (pinfunction "2_2") (pintype "input"))
      (node (ref "C11") (pin "2") (pinfunction "2_2") (pintype "input"))
      (node (ref "L3") (pin "2") (pinfunction "2_2") (pintype "input"))
      (node (ref "U1") (pin "19") (pinfunction "MICVDD_19") (pintype "unspecified"))
    )
    (net (code "36") (name "Net-(C27-Pad1)") (class "Default")
      (node (ref "C27") (pin "1") (pinfunction "1_1") (pintype "input"))
      (node (ref "R21") (pin "1") (pinfunction "1_1") (pintype "input"))
      (node (ref "R53") (pin "2") (pinfunction "2_2") (pintype "input"))
    )
    (net (code "37") (name "Net-(C27-Pad2)") (class "Default")
      (node (ref "C27") (pin "2") (pinfunction "2_2") (pintype "input"))
      (node (ref "R23") (pin "2") (pinfunction "2_2") (pintype "input"))
    )
    (net (code "38") (name "Net-(C28-Pad1)") (class "Default")
      (node (ref "C28") (pin "1") (pinfunction "1_1") (pintype "input"))
      (node (ref "R22") (pin "1") (pinfunction "1_1") (pintype "input"))
      (node (ref "R54") (pin "2") (pinfunction "2_2") (pintype "input"))
    )
    (net (code "39") (name "Net-(C28-Pad2)") (class "Default")
      (node (ref "C28") (pin "2") (pinfunction "2_2") (pintype "input"))
      (node (ref "R24") (pin "2") (pinfunction "2_2") (pintype "input"))
    )
    (net (code "40") (name "Net-(C40-Pad2)") (class "Default")
      (node (ref "C40") (pin "2") (pinfunction "2_2") (pintype "input"))
      (node (ref "C41") (pin "2") (pinfunction "2_2") (pintype "input"))
      (node (ref "R40") (pin "2") (pinfunction "2_2") (pintype "input"))
      (node (ref "R41") (pin "2") (pinfunction "2_2") (pintype "input"))
      (node (ref "R42") (pin "1") (pinfunction "1_1") (pintype "input"))
    )
    (net (code "41") (name "Net-(C50-Pad2)") (class "Default")
      (node (ref "C50") (pin "2") (pinfunction "2_2") (pintype "input"))
      (node (ref "C51") (pin "2") (pinfunction "2_2") (pintype "input"))
      (node (ref "R50") (pin "2") (pinfunction "2_2") (pintype "input"))
      (node (ref "R51") (pin "2") (pinfunction "2_2") (pintype "input"))
      (node (ref "R52") (pin "1") (pinfunction "1_1") (pintype "input"))
    )
    (net (code "42") (name "Net-(R55-Pad1)") (class "Default")
      (node (ref "R55") (pin "1") (pinfunction "1_1") (pintype "input"))
      (node (ref "U6") (pin "2") (pinfunction "2_2") (pintype "unspecified"))
    )
    (net (code "43") (name "Net-(R55-Pad2)") (class "Default")
      (node (ref "R55") (pin "2") (pinfunction "2_2") (pintype "input"))
      (node (ref "U16") (pin "1") (pinfunction "1_1") (pintype "unspecified"))
    )
    (net (code "44") (name "Net-(U1-VMIDC)") (class "Default")
      (node (ref "C3") (pin "1") (pinfunction "1_1") (pintype "input"))
      (node (ref "U1") (pin "21") (pinfunction "VMIDC_21") (pintype "unspecified"))
    )
    (net (code "45") (name "Net-(X1-OUT)") (class "Default")
      (node (ref "R5") (pin "2") (pinfunction "2_2") (pintype "input"))
      (node (ref "X1") (pin "3") (pinfunction "OUT_3") (pintype "unspecified"))
    )
    (net (code "46") (name "Net-(X1-VDD)") (class "Default")
      (node (ref "C1") (pin "1") (pinfunction "1_1") (pintype "input"))
      (node (ref "R4") (pin "1") (pinfunction "1_1") (pintype "input"))
      (node (ref "X1") (pin "4") (pinfunction "VDD_4") (pintype "unspecified"))
    )
    (net (code "47") (name "VCC_P1V8") (class "Default")
      (node (ref "C8") (pin "2") (pinfunction "2_2") (pintype "input"))
      (node (ref "L4") (pin "1") (pinfunction "1_1") (pintype "input"))
      (node (ref "L5") (pin "1") (pinfunction "1_1") (pintype "input"))
      (node (ref "L6") (pin "1") (pinfunction "1_1") (pintype "input"))
      (node (ref "R10") (pin "2") (pinfunction "2_2") (pintype "input"))
    )
    (net (code "48") (name "unconnected-(CN1-Pad1)") (class "Default")
      (node (ref "CN1") (pin "1") (pinfunction "1_1") (pintype "unspecified+no_connect"))
    )
    (net (code "49") (name "unconnected-(CN1-Pad5)") (class "Default")
      (node (ref "CN1") (pin "5") (pinfunction "5_5") (pintype "unspecified+no_connect"))
    )
    (net (code "50") (name "unconnected-(CN2-Pad1)") (class "Default")
      (node (ref "CN2") (pin "1") (pinfunction "1_1") (pintype "unspecified+no_connect"))
    )
    (net (code "51") (name "unconnected-(CN2-Pad5)") (class "Default")
      (node (ref "CN2") (pin "5") (pinfunction "5_5") (pintype "unspecified+no_connect"))
    )
    (net (code "52") (name "unconnected-(U1-IN1L{slash}DMICDAT1-Pad27)") (class "Default")
      (node (ref "U1") (pin "27") (pinfunction "IN1L/DMICDAT1_27") (pintype "unspecified+no_connect"))
    )
    (net (code "53") (name "unconnected-(U1-IN1R{slash}DMICDAT2-Pad25)") (class "Default")
      (node (ref "U1") (pin "25") (pinfunction "IN1R/DMICDAT2_25") (pintype "unspecified+no_connect"))
    )
    (net (code "54") (name "unconnected-(U1-LINEOUTL-Pad16)") (class "Default")
      (node (ref "U1") (pin "16") (pinfunction "LINEOUTL_16") (pintype "unspecified+no_connect"))
    )
    (net (code "55") (name "unconnected-(U1-LINEOUTR-Pad18)") (class "Default")
      (node (ref "U1") (pin "18") (pinfunction "LINEOUTR_18") (pintype "unspecified+no_connect"))
    )
    (net (code "56") (name "unconnected-(U6-Pad1)") (class "Default")
      (node (ref "U6") (pin "1") (pinfunction "1_1") (pintype "unspecified+no_connect"))
    )
    (net (code "57") (name "unconnected-(U7-Pad1)") (class "Default")
      (node (ref "U7") (pin "1") (pinfunction "1_1") (pintype "unspecified+no_connect"))
    )
    (net (code "58") (name "unconnected-(U7-Pad2)") (class "Default")
      (node (ref "U7") (pin "2") (pinfunction "2_2") (pintype "unspecified+no_connect"))
    )
    (net (code "59") (name "unconnected-(U7-Pad4)") (class "Default")
      (node (ref "U7") (pin "4") (pinfunction "4_4") (pintype "unspecified+no_connect"))
    )
    (net (code "60") (name "unconnected-(U7-Pad7)") (class "Default")
      (node (ref "U7") (pin "7") (pinfunction "7_7") (pintype "unspecified+no_connect"))
    )
    (net (code "61") (name "unconnected-(X1-{slash}ST-Pad1)") (class "Default")
      (node (ref "X1") (pin "1") (pinfunction "/ST_1") (pintype "unspecified+no_connect"))
    )
  )
)
